# lcd-breakoutboard.net
KiCad netlist of a schematic drawn in EAGLE
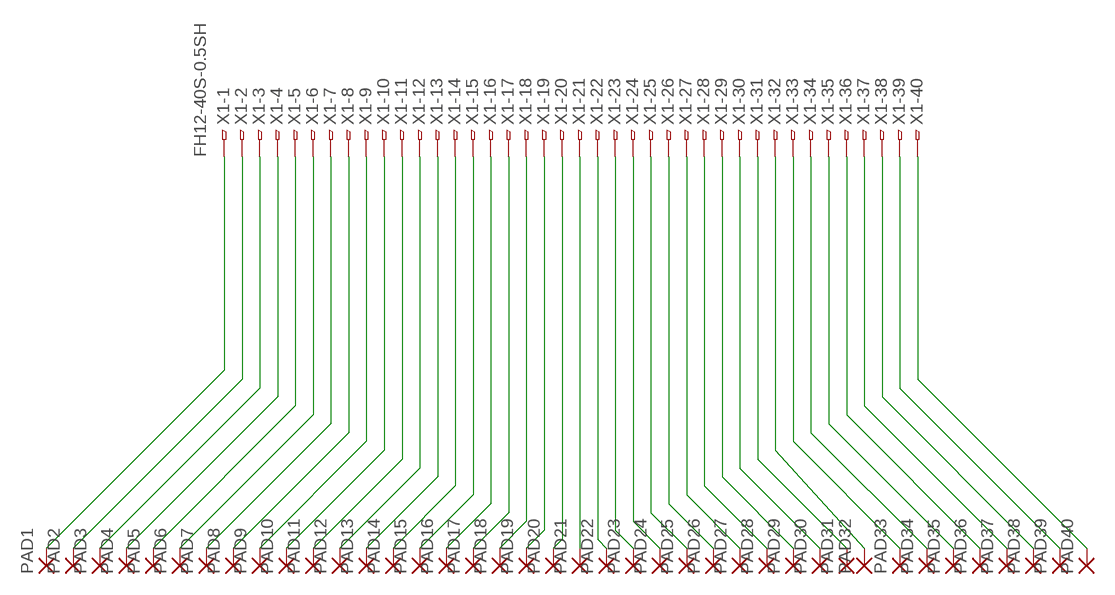
[diagram p0: schematic, sheet 1]

(export (version "E")
  (design (tool "Eeschema 10.0.6"))
  (components
    (comp (ref "PAD1")
      (value "2,15/1,0")
      (footprint "eagle-import:2,15_1,0")
      (libsource (lib "eagle-import") (part "2,15/1,0"))
    )
    (comp (ref "PAD2")
      (value "2,15/1,0")
      (footprint "eagle-import:2,15_1,0")
      (libsource (lib "eagle-import") (part "2,15/1,0"))
    )
    (comp (ref "PAD3")
      (value "2,15/1,0")
      (footprint "eagle-import:2,15_1,0")
      (libsource (lib "eagle-import") (part "2,15/1,0"))
    )
    (comp (ref "PAD4")
      (value "2,15/1,0")
      (footprint "eagle-import:2,15_1,0")
      (libsource (lib "eagle-import") (part "2,15/1,0"))
    )
    (comp (ref "PAD5")
      (value "2,15/1,0")
      (footprint "eagle-import:2,15_1,0")
      (libsource (lib "eagle-import") (part "2,15/1,0"))
    )
    (comp (ref "PAD6")
      (value "2,15/1,0")
      (footprint "eagle-import:2,15_1,0")
      (libsource (lib "eagle-import") (part "2,15/1,0"))
    )
    (comp (ref "PAD7")
      (value "2,15/1,0")
      (footprint "eagle-import:2,15_1,0")
      (libsource (lib "eagle-import") (part "2,15/1,0"))
    )
    (comp (ref "PAD8")
      (value "2,15/1,0")
      (footprint "eagle-import:2,15_1,0")
      (libsource (lib "eagle-import") (part "2,15/1,0"))
    )
    (comp (ref "PAD9")
      (value "2,15/1,0")
      (footprint "eagle-import:2,15_1,0")
      (libsource (lib "eagle-import") (part "2,15/1,0"))
    )
    (comp (ref "PAD10")
      (value "2,15/1,0")
      (footprint "eagle-import:2,15_1,0")
      (libsource (lib "eagle-import") (part "2,15/1,0"))
    )
    (comp (ref "PAD11")
      (value "2,15/1,0")
      (footprint "eagle-import:2,15_1,0")
      (libsource (lib "eagle-import") (part "2,15/1,0"))
    )
    (comp (ref "PAD12")
      (value "2,15/1,0")
      (footprint "eagle-import:2,15_1,0")
      (libsource (lib "eagle-import") (part "2,15/1,0"))
    )
    (comp (ref "PAD13")
      (value "2,15/1,0")
      (footprint "eagle-import:2,15_1,0")
      (libsource (lib "eagle-import") (part "2,15/1,0"))
    )
    (comp (ref "PAD14")
      (value "2,15/1,0")
      (footprint "eagle-import:2,15_1,0")
      (libsource (lib "eagle-import") (part "2,15/1,0"))
    )
    (comp (ref "PAD15")
      (value "2,15/1,0")
      (footprint "eagle-import:2,15_1,0")
      (libsource (lib "eagle-import") (part "2,15/1,0"))
    )
    (comp (ref "PAD16")
      (value "2,15/1,0")
      (footprint "eagle-import:2,15_1,0")
      (libsource (lib "eagle-import") (part "2,15/1,0"))
    )
    (comp (ref "PAD17")
      (value "2,15/1,0")
      (footprint "eagle-import:2,15_1,0")
      (libsource (lib "eagle-import") (part "2,15/1,0"))
    )
    (comp (ref "PAD18")
      (value "2,15/1,0")
      (footprint "eagle-import:2,15_1,0")
      (libsource (lib "eagle-import") (part "2,15/1,0"))
    )
    (comp (ref "PAD19")
      (value "2,15/1,0")
      (footprint "eagle-import:2,15_1,0")
      (libsource (lib "eagle-import") (part "2,15/1,0"))
    )
    (comp (ref "PAD20")
      (value "2,15/1,0")
      (footprint "eagle-import:2,15_1,0")
      (libsource (lib "eagle-import") (part "2,15/1,0"))
    )
    (comp (ref "PAD21")
      (value "2,15/1,0")
      (footprint "eagle-import:2,15_1,0")
      (libsource (lib "eagle-import") (part "2,15/1,0"))
    )
    (comp (ref "PAD22")
      (value "2,15/1,0")
      (footprint "eagle-import:2,15_1,0")
      (libsource (lib "eagle-import") (part "2,15/1,0"))
    )
    (comp (ref "PAD23")
      (value "2,15/1,0")
      (footprint "eagle-import:2,15_1,0")
      (libsource (lib "eagle-import") (part "2,15/1,0"))
    )
    (comp (ref "PAD24")
      (value "2,15/1,0")
      (footprint "eagle-import:2,15_1,0")
      (libsource (lib "eagle-import") (part "2,15/1,0"))
    )
    (comp (ref "PAD25")
      (value "2,15/1,0")
      (footprint "eagle-import:2,15_1,0")
      (libsource (lib "eagle-import") (part "2,15/1,0"))
    )
    (comp (ref "PAD26")
      (value "2,15/1,0")
      (footprint "eagle-import:2,15_1,0")
      (libsource (lib "eagle-import") (part "2,15/1,0"))
    )
    (comp (ref "PAD27")
      (value "2,15/1,0")
      (footprint "eagle-import:2,15_1,0")
      (libsource (lib "eagle-import") (part "2,15/1,0"))
    )
    (comp (ref "PAD28")
      (value "2,15/1,0")
      (footprint "eagle-import:2,15_1,0")
      (libsource (lib "eagle-import") (part "2,15/1,0"))
    )
    (comp (ref "PAD29")
      (value "2,15/1,0")
      (footprint "eagle-import:2,15_1,0")
      (libsource (lib "eagle-import") (part "2,15/1,0"))
    )
    (comp (ref "PAD30")
      (value "2,15/1,0")
      (footprint "eagle-import:2,15_1,0")
      (libsource (lib "eagle-import") (part "2,15/1,0"))
    )
    (comp (ref "PAD31")
      (value "2,15/1,0")
      (footprint "eagle-import:2,15_1,0")
      (libsource (lib "eagle-import") (part "2,15/1,0"))
    )
    (comp (ref "PAD32")
      (value "2,15/1,0")
      (footprint "eagle-import:2,15_1,0")
      (libsource (lib "eagle-import") (part "2,15/1,0"))
    )
    (comp (ref "PAD33")
      (value "2,15/1,0")
      (footprint "eagle-import:2,15_1,0")
      (libsource (lib "eagle-import") (part "2,15/1,0"))
    )
    (comp (ref "PAD34")
      (value "2,15/1,0")
      (footprint "eagle-import:2,15_1,0")
      (libsource (lib "eagle-import") (part "2,15/1,0"))
    )
    (comp (ref "PAD35")
      (value "2,15/1,0")
      (footprint "eagle-import:2,15_1,0")
      (libsource (lib "eagle-import") (part "2,15/1,0"))
    )
    (comp (ref "PAD36")
      (value "2,15/1,0")
      (footprint "eagle-import:2,15_1,0")
      (libsource (lib "eagle-import") (part "2,15/1,0"))
    )
    (comp (ref "PAD37")
      (value "2,15/1,0")
      (footprint "eagle-import:2,15_1,0")
      (libsource (lib "eagle-import") (part "2,15/1,0"))
    )
    (comp (ref "PAD38")
      (value "2,15/1,0")
      (footprint "eagle-import:2,15_1,0")
      (libsource (lib "eagle-import") (part "2,15/1,0"))
    )
    (comp (ref "PAD39")
      (value "2,15/1,0")
      (footprint "eagle-import:2,15_1,0")
      (libsource (lib "eagle-import") (part "2,15/1,0"))
    )
    (comp (ref "PAD40")
      (value "2,15/1,0")
      (footprint "eagle-import:2,15_1,0")
      (libsource (lib "eagle-import") (part "2,15/1,0"))
    )
    (comp (ref "X1")
      (value "FH12-40S-0.5SH")
      (footprint "eagle-import:FH12-40S-0.5SH")
      (fields (field (name "MPN") "FH12-40S-0.5SH(55)"))
      (libsource (lib "eagle-import") (part "FH12-40S-0.5SH"))
    )
  )
  (nets
    (net (code "1") (name "Net-(PAD1-P)") (class "Default")
      (node (ref "PAD1") (pin "1") (pinfunction "P_1") (pintype "passive"))
      (node (ref "X1") (pin "1") (pinfunction "1_1") (pintype "passive"))
    )
    (net (code "2") (name "Net-(PAD2-P)") (class "Default")
      (node (ref "PAD2") (pin "1") (pinfunction "P_1") (pintype "passive"))
      (node (ref "X1") (pin "2") (pinfunction "1_2") (pintype "passive"))
    )
    (net (code "3") (name "Net-(PAD3-P)") (class "Default")
      (node (ref "PAD3") (pin "1") (pinfunction "P_1") (pintype "passive"))
      (node (ref "X1") (pin "3") (pinfunction "1_3") (pintype "passive"))
    )
    (net (code "4") (name "Net-(PAD4-P)") (class "Default")
      (node (ref "PAD4") (pin "1") (pinfunction "P_1") (pintype "passive"))
      (node (ref "X1") (pin "4") (pinfunction "1_4") (pintype "passive"))
    )
    (net (code "5") (name "Net-(PAD5-P)") (class "Default")
      (node (ref "PAD5") (pin "1") (pinfunction "P_1") (pintype "passive"))
      (node (ref "X1") (pin "5") (pinfunction "1_5") (pintype "passive"))
    )
    (net (code "6") (name "Net-(PAD6-P)") (class "Default")
      (node (ref "PAD6") (pin "1") (pinfunction "P_1") (pintype "passive"))
      (node (ref "X1") (pin "6") (pinfunction "1_6") (pintype "passive"))
    )
    (net (code "7") (name "Net-(PAD7-P)") (class "Default")
      (node (ref "PAD7") (pin "1") (pinfunction "P_1") (pintype "passive"))
      (node (ref "X1") (pin "7") (pinfunction "1_7") (pintype "passive"))
    )
    (net (code "8") (name "Net-(PAD8-P)") (class "Default")
      (node (ref "PAD8") (pin "1") (pinfunction "P_1") (pintype "passive"))
      (node (ref "X1") (pin "8") (pinfunction "1_8") (pintype "passive"))
    )
    (net (code "9") (name "Net-(PAD9-P)") (class "Default")
      (node (ref "PAD9") (pin "1") (pinfunction "P_1") (pintype "passive"))
      (node (ref "X1") (pin "9") (pinfunction "1_9") (pintype "passive"))
    )
    (net (code "10") (name "Net-(PAD10-P)") (class "Default")
      (node (ref "PAD10") (pin "1") (pinfunction "P_1") (pintype "passive"))
      (node (ref "X1") (pin "10") (pinfunction "1_10") (pintype "passive"))
    )
    (net (code "11") (name "Net-(PAD11-P)") (class "Default")
      (node (ref "PAD11") (pin "1") (pinfunction "P_1") (pintype "passive"))
      (node (ref "X1") (pin "11") (pinfunction "1_11") (pintype "passive"))
    )
    (net (code "12") (name "Net-(PAD12-P)") (class "Default")
      (node (ref "PAD12") (pin "1") (pinfunction "P_1") (pintype "passive"))
      (node (ref "X1") (pin "12") (pinfunction "1_12") (pintype "passive"))
    )
    (net (code "13") (name "Net-(PAD13-P)") (class "Default")
      (node (ref "PAD13") (pin "1") (pinfunction "P_1") (pintype "passive"))
      (node (ref "X1") (pin "13") (pinfunction "1_13") (pintype "passive"))
    )
    (net (code "14") (name "Net-(PAD14-P)") (class "Default")
      (node (ref "PAD14") (pin "1") (pinfunction "P_1") (pintype "passive"))
      (node (ref "X1") (pin "14") (pinfunction "1_14") (pintype "passive"))
    )
    (net (code "15") (name "Net-(PAD15-P)") (class "Default")
      (node (ref "PAD15") (pin "1") (pinfunction "P_1") (pintype "passive"))
      (node (ref "X1") (pin "15") (pinfunction "1_15") (pintype "passive"))
    )
    (net (code "16") (name "Net-(PAD16-P)") (class "Default")
      (node (ref "PAD16") (pin "1") (pinfunction "P_1") (pintype "passive"))
      (node (ref "X1") (pin "16") (pinfunction "1_16") (pintype "passive"))
    )
    (net (code "17") (name "Net-(PAD17-P)") (class "Default")
      (node (ref "PAD17") (pin "1") (pinfunction "P_1") (pintype "passive"))
      (node (ref "X1") (pin "17") (pinfunction "1_17") (pintype "passive"))
    )
    (net (code "18") (name "Net-(PAD18-P)") (class "Default")
      (node (ref "PAD18") (pin "1") (pinfunction "P_1") (pintype "passive"))
      (node (ref "X1") (pin "18") (pinfunction "1_18") (pintype "passive"))
    )
    (net (code "19") (name "Net-(PAD19-P)") (class "Default")
      (node (ref "PAD19") (pin "1") (pinfunction "P_1") (pintype "passive"))
      (node (ref "X1") (pin "19") (pinfunction "1_19") (pintype "passive"))
    )
    (net (code "20") (name "Net-(PAD20-P)") (class "Default")
      (node (ref "PAD20") (pin "1") (pinfunction "P_1") (pintype "passive"))
      (node (ref "X1") (pin "20") (pinfunction "1_20") (pintype "passive"))
    )
    (net (code "21") (name "Net-(PAD21-P)") (class "Default")
      (node (ref "PAD21") (pin "1") (pinfunction "P_1") (pintype "passive"))
      (node (ref "X1") (pin "21") (pinfunction "1_21") (pintype "passive"))
    )
    (net (code "22") (name "Net-(PAD22-P)") (class "Default")
      (node (ref "PAD22") (pin "1") (pinfunction "P_1") (pintype "passive"))
      (node (ref "X1") (pin "22") (pinfunction "1_22") (pintype "passive"))
    )
    (net (code "23") (name "Net-(PAD23-P)") (class "Default")
      (node (ref "PAD23") (pin "1") (pinfunction "P_1") (pintype "passive"))
      (node (ref "X1") (pin "23") (pinfunction "1_23") (pintype "passive"))
    )
    (net (code "24") (name "Net-(PAD24-P)") (class "Default")
      (node (ref "PAD24") (pin "1") (pinfunction "P_1") (pintype "passive"))
      (node (ref "X1") (pin "24") (pinfunction "1_24") (pintype "passive"))
    )
    (net (code "25") (name "Net-(PAD25-P)") (class "Default")
      (node (ref "PAD25") (pin "1") (pinfunction "P_1") (pintype "passive"))
      (node (ref "X1") (pin "25") (pinfunction "1_25") (pintype "passive"))
    )
    (net (code "26") (name "Net-(PAD26-P)") (class "Default")
      (node (ref "PAD26") (pin "1") (pinfunction "P_1") (pintype "passive"))
      (node (ref "X1") (pin "26") (pinfunction "1_26") (pintype "passive"))
    )
    (net (code "27") (name "Net-(PAD27-P)") (class "Default")
      (node (ref "PAD27") (pin "1") (pinfunction "P_1") (pintype "passive"))
      (node (ref "X1") (pin "27") (pinfunction "1_27") (pintype "passive"))
    )
    (net (code "28") (name "Net-(PAD28-P)") (class "Default")
      (node (ref "PAD28") (pin "1") (pinfunction "P_1") (pintype "passive"))
      (node (ref "X1") (pin "28") (pinfunction "1_28") (pintype "passive"))
    )
    (net (code "29") (name "Net-(PAD29-P)") (class "Default")
      (node (ref "PAD29") (pin "1") (pinfunction "P_1") (pintype "passive"))
      (node (ref "X1") (pin "29") (pinfunction "1_29") (pintype "passive"))
    )
    (net (code "30") (name "Net-(PAD30-P)") (class "Default")
      (node (ref "PAD30") (pin "1") (pinfunction "P_1") (pintype "passive"))
      (node (ref "X1") (pin "30") (pinfunction "1_30") (pintype "passive"))
    )
    (net (code "31") (name "Net-(PAD31-P)") (class "Default")
      (node (ref "PAD31") (pin "1") (pinfunction "P_1") (pintype "passive"))
      (node (ref "X1") (pin "31") (pinfunction "1_31") (pintype "passive"))
    )
    (net (code "32") (name "Net-(PAD32-P)") (class "Default")
      (node (ref "PAD32") (pin "1") (pinfunction "P_1") (pintype "passive"))
      (node (ref "X1") (pin "32") (pinfunction "1_32") (pintype "passive"))
    )
    (net (code "33") (name "Net-(PAD33-P)") (class "Default")
      (node (ref "PAD33") (pin "1") (pinfunction "P_1") (pintype "passive"))
      (node (ref "X1") (pin "33") (pinfunction "1_33") (pintype "passive"))
    )
    (net (code "34") (name "Net-(PAD34-P)") (class "Default")
      (node (ref "PAD34") (pin "1") (pinfunction "P_1") (pintype "passive"))
      (node (ref "X1") (pin "34") (pinfunction "1_34") (pintype "passive"))
    )
    (net (code "35") (name "Net-(PAD35-P)") (class "Default")
      (node (ref "PAD35") (pin "1") (pinfunction "P_1") (pintype "passive"))
      (node (ref "X1") (pin "35") (pinfunction "1_35") (pintype "passive"))
    )
    (net (code "36") (name "Net-(PAD36-P)") (class "Default")
      (node (ref "PAD36") (pin "1") (pinfunction "P_1") (pintype "passive"))
      (node (ref "X1") (pin "36") (pinfunction "1_36") (pintype "passive"))
    )
    (net (code "37") (name "Net-(PAD37-P)") (class "Default")
      (node (ref "PAD37") (pin "1") (pinfunction "P_1") (pintype "passive"))
      (node (ref "X1") (pin "37") (pinfunction "1_37") (pintype "passive"))
    )
    (net (code "38") (name "Net-(PAD38-P)") (class "Default")
      (node (ref "PAD38") (pin "1") (pinfunction "P_1") (pintype "passive"))
      (node (ref "X1") (pin "38") (pinfunction "1_38") (pintype "passive"))
    )
    (net (code "39") (name "Net-(PAD39-P)") (class "Default")
      (node (ref "PAD39") (pin "1") (pinfunction "P_1") (pintype "passive"))
      (node (ref "X1") (pin "39") (pinfunction "1_39") (pintype "passive"))
    )
    (net (code "40") (name "Net-(PAD40-P)") (class "Default")
      (node (ref "PAD40") (pin "1") (pinfunction "P_1") (pintype "passive"))
      (node (ref "X1") (pin "40") (pinfunction "1_40") (pintype "passive"))
    )
  )
)
